# BATT_MONITOR.net
KiCad netlist of a schematic drawn in EAGLE
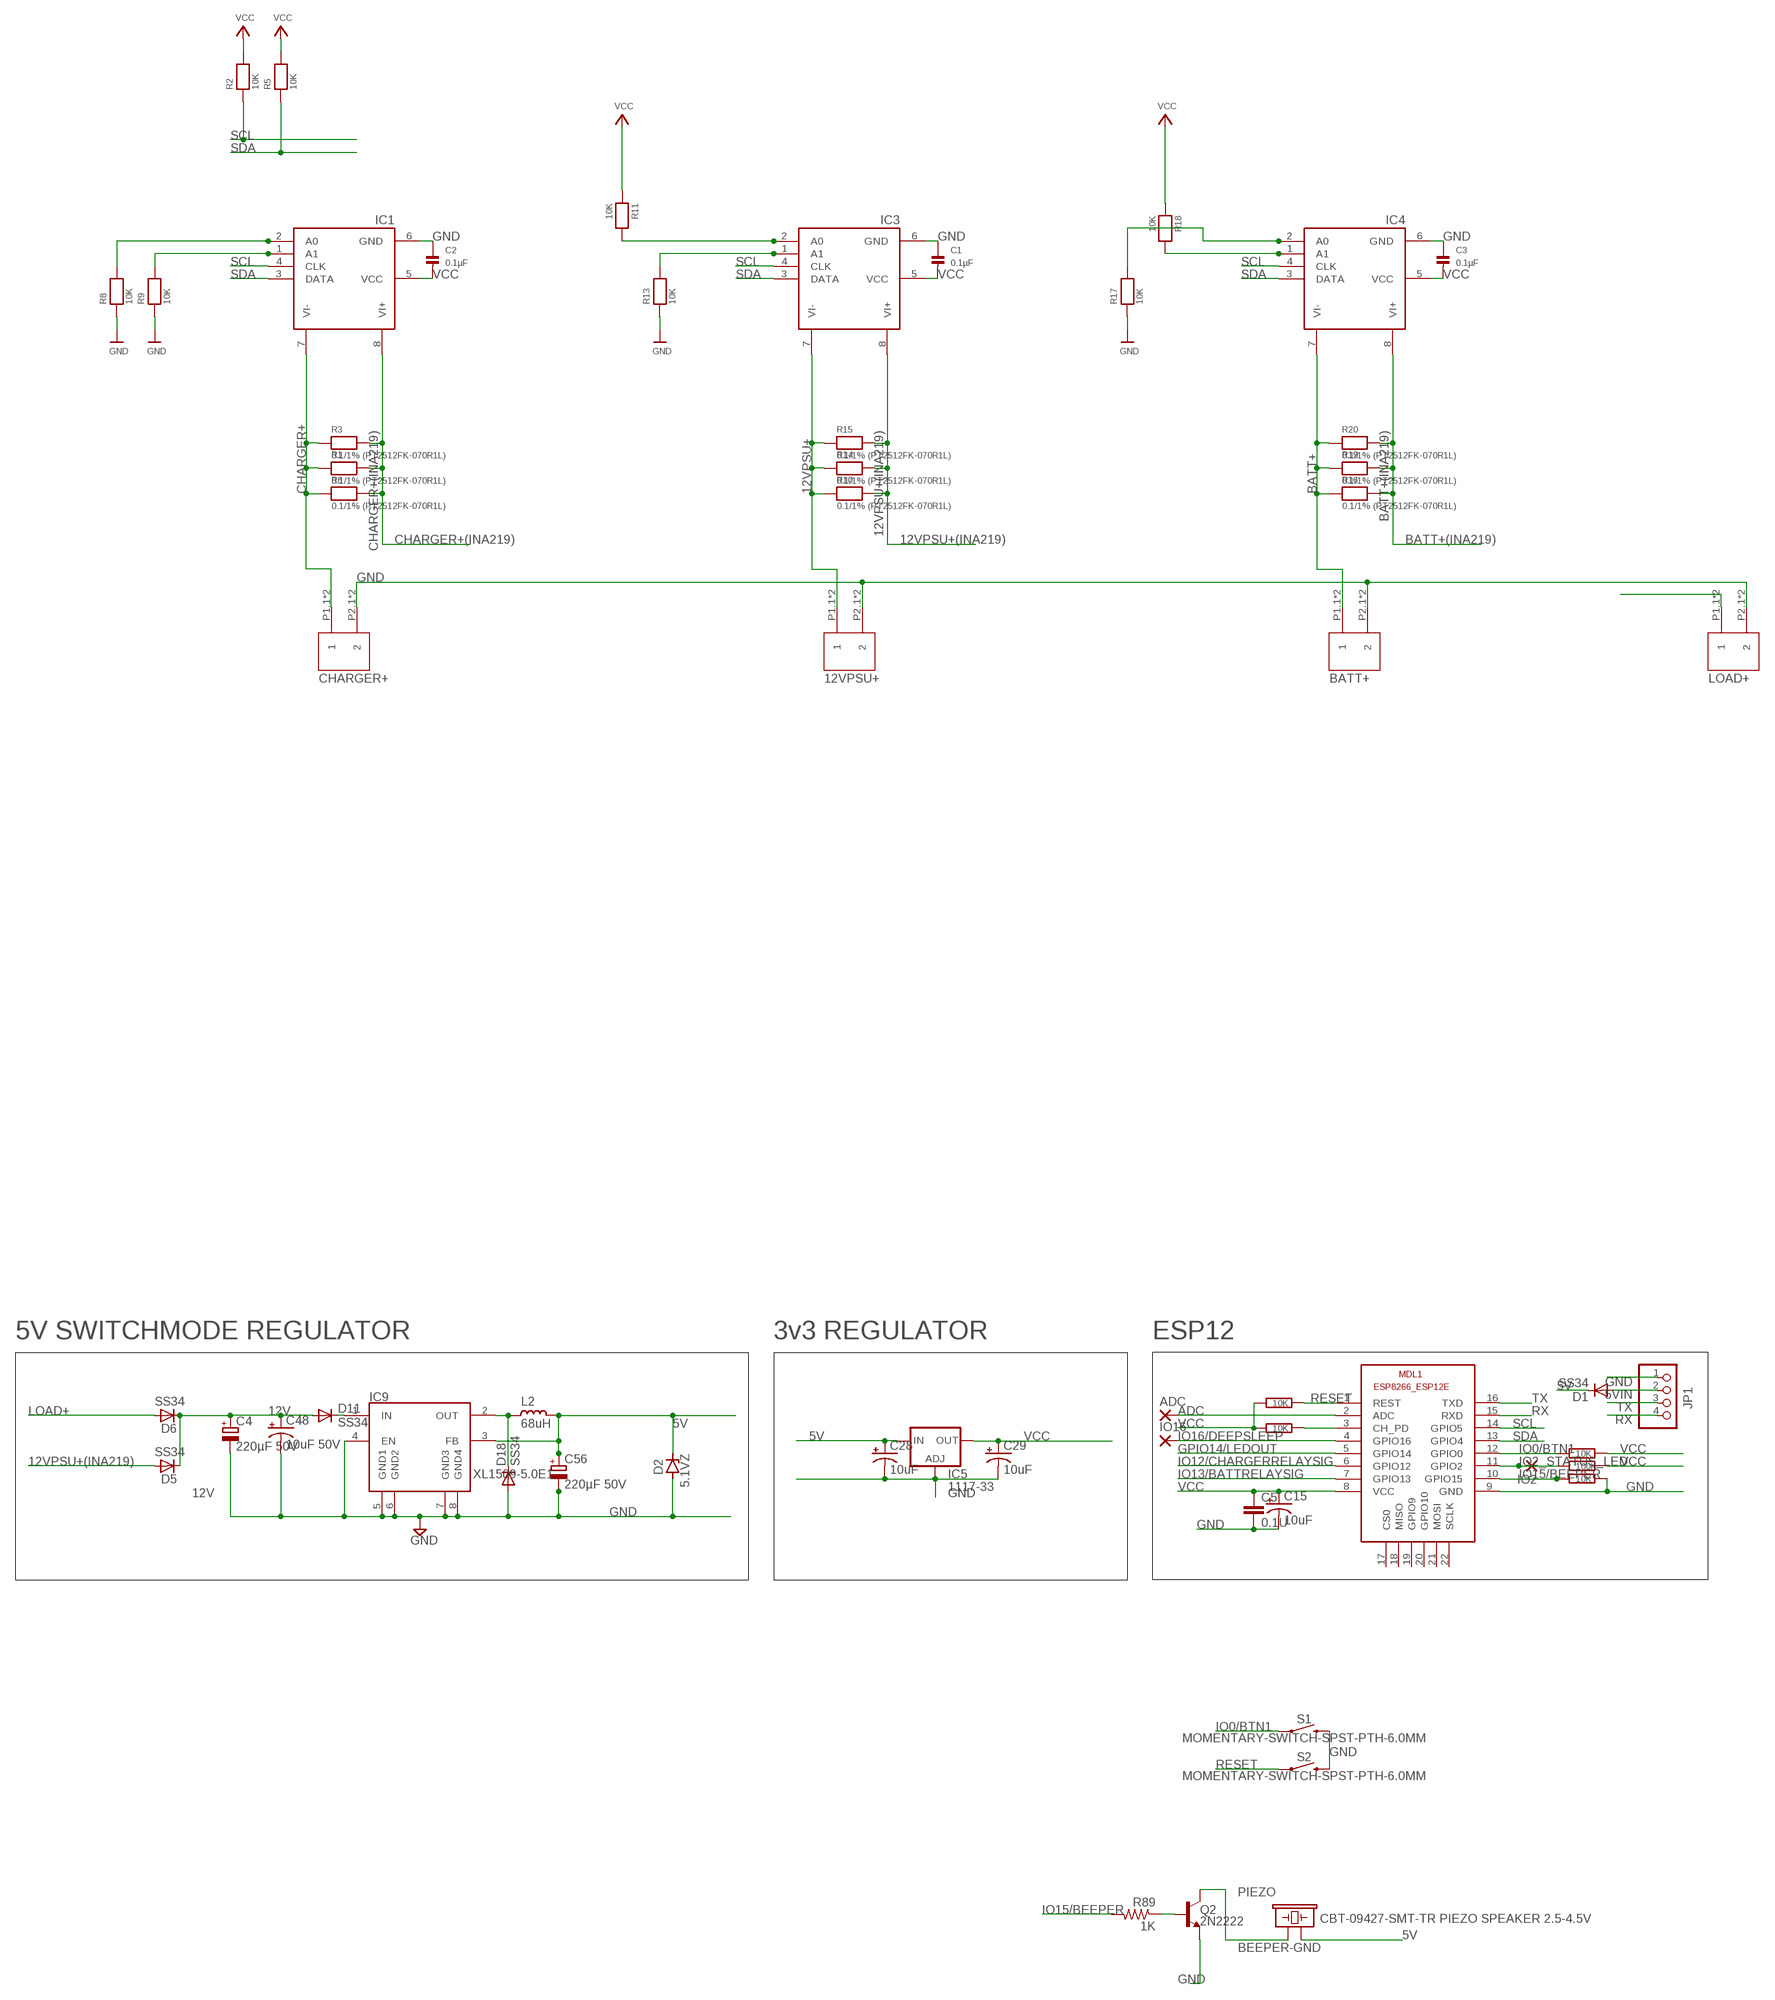
[diagram p0: schematic, sheet 2, part 1 of 2]
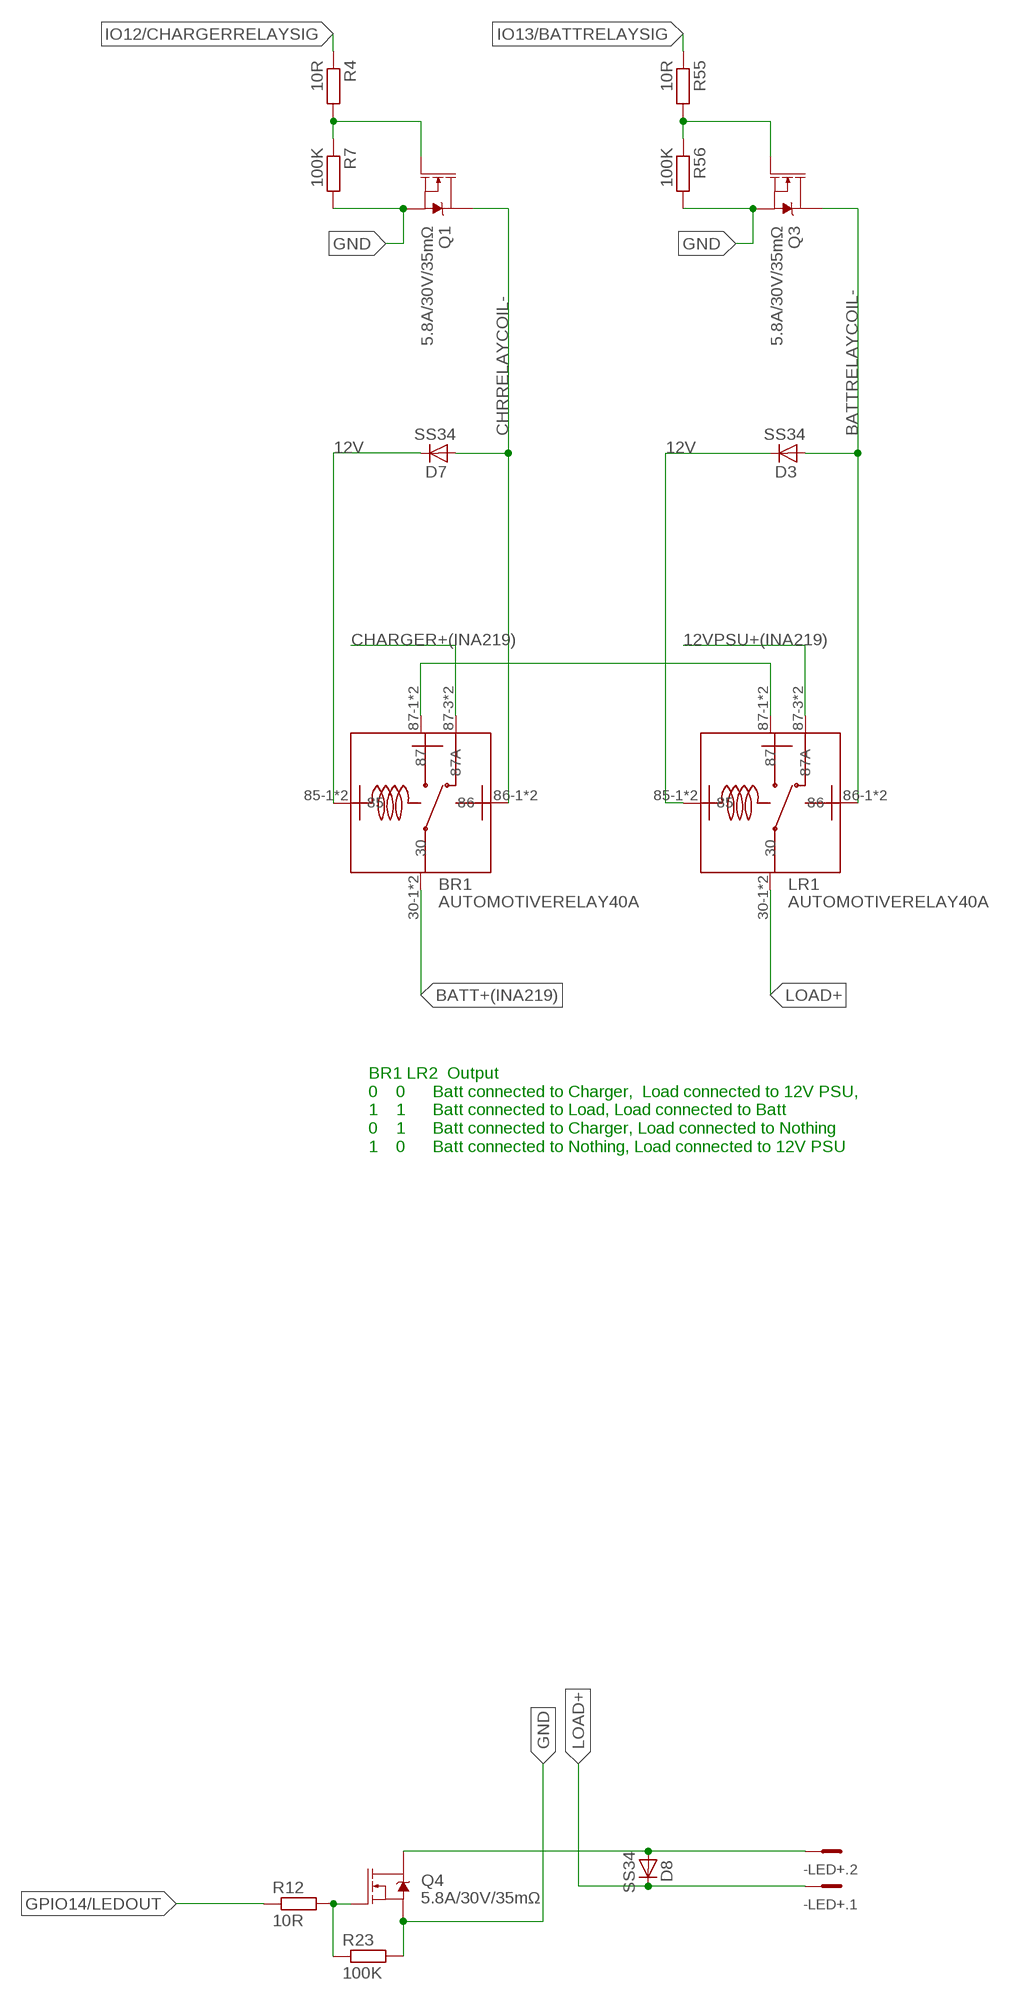
[diagram p1: schematic, sheet 2, part 2 of 2]

(export (version "E")
  (design (tool "Eeschema 10.0.6"))
  (components
    (comp (ref "-LED+")
      (value "MCV2")
      (footprint "eagle-import:MCV2")
      (libsource (lib "eagle-import") (part "MCV2"))
    )
    (comp (ref "ADC")
      (value "2,54/1,1")
      (footprint "eagle-import:2,54_1,1")
      (libsource (lib "eagle-import") (part "2,54/1,1"))
    )
    (comp (ref "BR1")
      (value "AUTOMOTIVERELAY40A")
      (footprint "eagle-import:AUTOMOTIVERELAY40A")
      (libsource (lib "eagle-import") (part "AUTOMOTIVERELAY40A"))
    )
    (comp (ref "C1")
      (value "0.1µF")
      (footprint "eagle-import:1206")
      (libsource (lib "eagle-import") (part "CAP_CERAMIC1206"))
    )
    (comp (ref "C2")
      (value "0.1µF")
      (footprint "eagle-import:1206")
      (libsource (lib "eagle-import") (part "CAP_CERAMIC1206"))
    )
    (comp (ref "C3")
      (value "0.1µF")
      (footprint "eagle-import:1206")
      (libsource (lib "eagle-import") (part "CAP_CERAMIC1206"))
    )
    (comp (ref "C4")
      (value "220µF 50V")
      (footprint "eagle-import:E3,5-10")
      (libsource (lib "eagle-import") (part "CPOL-EUE3.5-10"))
    )
    (comp (ref "C5")
      (value "0.1U")
      (footprint "eagle-import:C1206")
      (libsource (lib "eagle-import") (part "C-EUC1206"))
    )
    (comp (ref "C15")
      (value "10uF")
      (footprint "eagle-import:EIA3216")
      (libsource (lib "eagle-import") (part "CAP_POL1206"))
    )
    (comp (ref "C28")
      (value "10uF")
      (footprint "eagle-import:EIA3216")
      (libsource (lib "eagle-import") (part "CAP_POL1206"))
    )
    (comp (ref "C29")
      (value "10uF")
      (footprint "eagle-import:EIA3216")
      (libsource (lib "eagle-import") (part "CAP_POL1206"))
    )
    (comp (ref "C48")
      (value "10uF 50V")
      (footprint "eagle-import:EIA3216")
      (libsource (lib "eagle-import") (part "CAP_POL1206"))
    )
    (comp (ref "C56")
      (value "220µF 50V")
      (footprint "eagle-import:E3,5-10")
      (libsource (lib "eagle-import") (part "CPOL-EUE3.5-10"))
    )
    (comp (ref "CHARGER1")
      (value "BARRIERTERMINAL")
      (footprint "eagle-import:BARRIERTERMINAL")
      (libsource (lib "eagle-import") (part "BARRIERTERMINAL"))
    )
    (comp (ref "CHARGER2")
      (value "BARRIERTERMINAL")
      (footprint "eagle-import:BARRIERTERMINAL")
      (libsource (lib "eagle-import") (part "BARRIERTERMINAL"))
    )
    (comp (ref "CHARGER3")
      (value "BARRIERTERMINAL")
      (footprint "eagle-import:BARRIERTERMINAL")
      (libsource (lib "eagle-import") (part "BARRIERTERMINAL"))
    )
    (comp (ref "CHARGER4")
      (value "BARRIERTERMINAL")
      (footprint "eagle-import:BARRIERTERMINAL")
      (libsource (lib "eagle-import") (part "BARRIERTERMINAL"))
    )
    (comp (ref "D1")
      (value "SS34")
      (footprint "eagle-import:DO-214AC")
      (libsource (lib "eagle-import") (part "DIODE-DO-214AC"))
    )
    (comp (ref "D2")
      (value "5.1VZ")
      (footprint "eagle-import:SMB")
      (libsource (lib "eagle-import") (part "ZENER-DIODESMB"))
    )
    (comp (ref "D3")
      (value "SS34")
      (footprint "eagle-import:SOD87")
      (libsource (lib "eagle-import") (part "D-SOD-87"))
    )
    (comp (ref "D5")
      (value "SS34")
      (footprint "eagle-import:SOD87")
      (libsource (lib "eagle-import") (part "D-SOD-87"))
    )
    (comp (ref "D6")
      (value "SS34")
      (footprint "eagle-import:SOD87")
      (libsource (lib "eagle-import") (part "D-SOD-87"))
    )
    (comp (ref "D7")
      (value "SS34")
      (footprint "eagle-import:SOD87")
      (libsource (lib "eagle-import") (part "D-SOD-87"))
    )
    (comp (ref "D8")
      (value "SS34")
      (footprint "eagle-import:SOD87")
      (libsource (lib "eagle-import") (part "D-SOD-87"))
    )
    (comp (ref "D11")
      (value "SS34")
      (footprint "eagle-import:DO-214AC")
      (libsource (lib "eagle-import") (part "DIODE-DO-214AC"))
    )
    (comp (ref "D18")
      (value "SS34")
      (footprint "eagle-import:DO-214AC")
      (libsource (lib "eagle-import") (part "DIODE-DO-214AC"))
    )
    (comp (ref "IC1")
      (value "INA219D")
      (footprint "eagle-import:SO08")
      (libsource (lib "eagle-import") (part "INA219D"))
    )
    (comp (ref "IC3")
      (value "INA219D")
      (footprint "eagle-import:SO08")
      (libsource (lib "eagle-import") (part "INA219D"))
    )
    (comp (ref "IC4")
      (value "INA219D")
      (footprint "eagle-import:SO08")
      (libsource (lib "eagle-import") (part "INA219D"))
    )
    (comp (ref "IC5")
      (value "1117-33")
      (footprint "eagle-import:SOT223")
      (libsource (lib "eagle-import") (part "LD117A?S33TR"))
    )
    (comp (ref "IC9")
      (value "XL1509-5.0E1")
      (footprint "eagle-import:SO08")
      (libsource (lib "eagle-import") (part "XL1509"))
    )
    (comp (ref "IO2")
      (value "2,54/1,1")
      (footprint "eagle-import:2,54_1,1")
      (libsource (lib "eagle-import") (part "2,54/1,1"))
    )
    (comp (ref "IO16")
      (value "2,54/1,1")
      (footprint "eagle-import:2,54_1,1")
      (libsource (lib "eagle-import") (part "2,54/1,1"))
    )
    (comp (ref "JP1")
      (value "PINHD-1X4")
      (footprint "eagle-import:1X04")
      (libsource (lib "eagle-import") (part "PINHD-1X4"))
    )
    (comp (ref "L2")
      (value "68uH")
      (footprint "eagle-import:CD75")
      (libsource (lib "eagle-import") (part "L_CD75"))
    )
    (comp (ref "LR1")
      (value "AUTOMOTIVERELAY40A")
      (footprint "eagle-import:AUTOMOTIVERELAY40A")
      (libsource (lib "eagle-import") (part "AUTOMOTIVERELAY40A"))
    )
    (comp (ref "MDL1")
      (value "ESP8266-12EESP8266-ESP12E")
      (footprint "eagle-import:ESP8266-ESP12E")
      (libsource (lib "eagle-import") (part "ESP8266-12EESP8266-ESP12E"))
    )
    (comp (ref "PIEZO")
      (value "CBT-09427-SMT-TR PIEZO SPEAKER 2.5-4.5V")
      (footprint "eagle-import:BUZZER-12MM")
      (libsource (lib "eagle-import") (part "BUZZER-PTH"))
    )
    (comp (ref "Q1")
      (value "5.8A/30V/35mΩ")
      (footprint "eagle-import:SOT23-3")
      (libsource (lib "eagle-import") (part "MOSFET-NCH-AO3404A"))
    )
    (comp (ref "Q2")
      (value "2N2222")
      (footprint "eagle-import:SOT23-3")
      (libsource (lib "eagle-import") (part "TRANS_NPN-MMBT2222AL"))
    )
    (comp (ref "Q3")
      (value "5.8A/30V/35mΩ")
      (footprint "eagle-import:SOT23-3")
      (libsource (lib "eagle-import") (part "MOSFET-NCH-AO3404A"))
    )
    (comp (ref "Q4")
      (value "5.8A/30V/35mΩ")
      (footprint "eagle-import:SOT23-3")
      (libsource (lib "eagle-import") (part "MOSFET-NCH-AO3404A"))
    )
    (comp (ref "R1")
      (value "0.1/1% (PT2512FK-070R1L)")
      (footprint "eagle-import:2512")
      (libsource (lib "eagle-import") (part "RESISTOR2512"))
    )
    (comp (ref "R2")
      (value "10K")
      (footprint "eagle-import:1206")
      (libsource (lib "eagle-import") (part "RESISTOR1206"))
    )
    (comp (ref "R3")
      (value "0.1/1% (PT2512FK-070R1L)")
      (footprint "eagle-import:2512")
      (libsource (lib "eagle-import") (part "RESISTOR2512"))
    )
    (comp (ref "R4")
      (value "10R")
      (footprint "eagle-import:R1206")
      (libsource (lib "eagle-import") (part "rcl_334_R-EU_R1206"))
    )
    (comp (ref "R5")
      (value "10K")
      (footprint "eagle-import:1206")
      (libsource (lib "eagle-import") (part "RESISTOR1206"))
    )
    (comp (ref "R6")
      (value "0.1/1% (PT2512FK-070R1L)")
      (footprint "eagle-import:2512")
      (libsource (lib "eagle-import") (part "RESISTOR2512"))
    )
    (comp (ref "R7")
      (value "100K")
      (footprint "eagle-import:R1206")
      (libsource (lib "eagle-import") (part "rcl_334_R-EU_R1206"))
    )
    (comp (ref "R8")
      (value "10K")
      (footprint "eagle-import:1206")
      (libsource (lib "eagle-import") (part "RESISTOR1206"))
    )
    (comp (ref "R9")
      (value "10K")
      (footprint "eagle-import:1206")
      (libsource (lib "eagle-import") (part "RESISTOR1206"))
    )
    (comp (ref "R10")
      (value "0.1/1% (PT2512FK-070R1L)")
      (footprint "eagle-import:2512")
      (libsource (lib "eagle-import") (part "RESISTOR2512"))
    )
    (comp (ref "R11")
      (value "10K")
      (footprint "eagle-import:1206")
      (libsource (lib "eagle-import") (part "RESISTOR1206"))
    )
    (comp (ref "R12")
      (value "10R")
      (footprint "eagle-import:M1206")
      (libsource (lib "eagle-import") (part "rcl_334_R-EU_M1206"))
    )
    (comp (ref "R13")
      (value "10K")
      (footprint "eagle-import:1206")
      (libsource (lib "eagle-import") (part "RESISTOR1206"))
    )
    (comp (ref "R14")
      (value "0.1/1% (PT2512FK-070R1L)")
      (footprint "eagle-import:2512")
      (libsource (lib "eagle-import") (part "RESISTOR2512"))
    )
    (comp (ref "R15")
      (value "0.1/1% (PT2512FK-070R1L)")
      (footprint "eagle-import:2512")
      (libsource (lib "eagle-import") (part "RESISTOR2512"))
    )
    (comp (ref "R16")
      (value "0.1/1% (PT2512FK-070R1L)")
      (footprint "eagle-import:2512")
      (libsource (lib "eagle-import") (part "RESISTOR2512"))
    )
    (comp (ref "R17")
      (value "10K")
      (footprint "eagle-import:1206")
      (libsource (lib "eagle-import") (part "RESISTOR1206"))
    )
    (comp (ref "R18")
      (value "10K")
      (footprint "eagle-import:1206")
      (libsource (lib "eagle-import") (part "RESISTOR1206"))
    )
    (comp (ref "R19")
      (value "0.1/1% (PT2512FK-070R1L)")
      (footprint "eagle-import:2512")
      (libsource (lib "eagle-import") (part "RESISTOR2512"))
    )
    (comp (ref "R20")
      (value "0.1/1% (PT2512FK-070R1L)")
      (footprint "eagle-import:2512")
      (libsource (lib "eagle-import") (part "RESISTOR2512"))
    )
    (comp (ref "R21")
      (value "100K")
      (footprint "eagle-import:R1206")
      (libsource (lib "eagle-import") (part "R-EU_R1206"))
    )
    (comp (ref "R22")
      (value "10K")
      (footprint "eagle-import:R1206")
      (libsource (lib "eagle-import") (part "R-EU_R1206"))
    )
    (comp (ref "R23")
      (value "100K")
      (footprint "eagle-import:M1206")
      (libsource (lib "eagle-import") (part "rcl_334_R-EU_M1206"))
    )
    (comp (ref "R28")
      (value "10K")
      (footprint "eagle-import:R1206")
      (libsource (lib "eagle-import") (part "R-EU_R1206"))
    )
    (comp (ref "R29")
      (value "10K")
      (footprint "eagle-import:R1206")
      (libsource (lib "eagle-import") (part "R-EU_R1206"))
    )
    (comp (ref "R31")
      (value "10K")
      (footprint "eagle-import:R1206")
      (libsource (lib "eagle-import") (part "R-EU_R1206"))
    )
    (comp (ref "R55")
      (value "10R")
      (footprint "eagle-import:R1206")
      (libsource (lib "eagle-import") (part "rcl_334_R-EU_R1206"))
    )
    (comp (ref "R56")
      (value "100K")
      (footprint "eagle-import:R1206")
      (libsource (lib "eagle-import") (part "rcl_334_R-EU_R1206"))
    )
    (comp (ref "R89")
      (value "1K")
      (footprint "eagle-import:R1206")
      (libsource (lib "eagle-import") (part "R-US_R1206"))
    )
    (comp (ref "S1")
      (value "MOMENTARY-SWITCH-SPST-PTH-6.0MM")
      (footprint "eagle-import:TACTILE_SWITCH_PTH_6.0MM")
      (libsource (lib "eagle-import") (part "MOMENTARY-SWITCH-SPST-PTH-6.0MM"))
    )
    (comp (ref "S2")
      (value "MOMENTARY-SWITCH-SPST-PTH-6.0MM")
      (footprint "eagle-import:TACTILE_SWITCH_PTH_6.0MM")
      (libsource (lib "eagle-import") (part "MOMENTARY-SWITCH-SPST-PTH-6.0MM"))
    )
  )
  (nets
    (net (code "1") (name "5V") (class "Default")
      (node (ref "C28") (pin "A") (pinfunction "+_A") (pintype "passive"))
      (node (ref "C56") (pin "+") (pinfunction "+_+") (pintype "passive"))
      (node (ref "D1") (pin "1") (pinfunction "C_1") (pintype "passive"))
      (node (ref "D2") (pin "C") (pinfunction "C_C") (pintype "passive"))
      (node (ref "IC5") (pin "3") (pinfunction "IN_3") (pintype "input"))
      (node (ref "IC9") (pin "3") (pinfunction "FB_3") (pintype "bidirectional"))
      (node (ref "L2") (pin "1") (pinfunction "1_1") (pintype "passive"))
      (node (ref "PIEZO") (pin "+") (pinfunction "1_+") (pintype "passive"))
    )
    (net (code "2") (name "5VIN") (class "Default")
      (node (ref "D1") (pin "2") (pinfunction "A_2") (pintype "passive"))
      (node (ref "JP1") (pin "2") (pinfunction "2_2") (pintype "passive"))
    )
    (net (code "3") (name "12V") (class "Default")
      (node (ref "BR1") (pin "85-1") (pinfunction "85_85-1") (pintype "bidirectional"))
      (node (ref "BR1") (pin "85-2") (pinfunction "85_85-2") (pintype "bidirectional"))
      (node (ref "C4") (pin "+") (pinfunction "+_+") (pintype "passive"))
      (node (ref "C48") (pin "A") (pinfunction "+_A") (pintype "passive"))
      (node (ref "D11") (pin "2") (pinfunction "A_2") (pintype "passive"))
      (node (ref "D3") (pin "1") (pinfunction "C_1") (pintype "passive"))
      (node (ref "D5") (pin "1") (pinfunction "C_1") (pintype "passive"))
      (node (ref "D6") (pin "1") (pinfunction "C_1") (pintype "passive"))
      (node (ref "D7") (pin "1") (pinfunction "C_1") (pintype "passive"))
      (node (ref "LR1") (pin "85-1") (pinfunction "85_85-1") (pintype "bidirectional"))
      (node (ref "LR1") (pin "85-2") (pinfunction "85_85-2") (pintype "bidirectional"))
    )
    (net (code "4") (name "12VPSU+") (class "Default")
      (node (ref "CHARGER4") (pin "P1.1") (pinfunction "1_P1.1") (pintype "bidirectional"))
      (node (ref "CHARGER4") (pin "P1.2") (pinfunction "1_P1.2") (pintype "bidirectional"))
      (node (ref "IC3") (pin "7") (pinfunction "VI-_7") (pintype "input"))
      (node (ref "R10") (pin "1") (pinfunction "1_1") (pintype "passive"))
      (node (ref "R14") (pin "1") (pinfunction "1_1") (pintype "passive"))
      (node (ref "R15") (pin "1") (pinfunction "1_1") (pintype "passive"))
    )
    (net (code "5") (name "12VPSU+(INA219)") (class "Default")
      (node (ref "D5") (pin "2") (pinfunction "A_2") (pintype "passive"))
      (node (ref "IC3") (pin "8") (pinfunction "VI+_8") (pintype "input"))
      (node (ref "LR1") (pin "87-3") (pinfunction "87A_87-3") (pintype "bidirectional"))
      (node (ref "LR1") (pin "87-4") (pinfunction "87A_87-4") (pintype "bidirectional"))
      (node (ref "R10") (pin "2") (pinfunction "2_2") (pintype "passive"))
      (node (ref "R14") (pin "2") (pinfunction "2_2") (pintype "passive"))
      (node (ref "R15") (pin "2") (pinfunction "2_2") (pintype "passive"))
    )
    (net (code "6") (name "ADC") (class "Default")
      (node (ref "ADC") (pin "1") (pinfunction "P_1") (pintype "passive"))
      (node (ref "MDL1") (pin "2") (pinfunction "ADC_2") (pintype "bidirectional"))
    )
    (net (code "7") (name "BATT+") (class "Default")
      (node (ref "CHARGER1") (pin "P1.1") (pinfunction "1_P1.1") (pintype "bidirectional"))
      (node (ref "CHARGER1") (pin "P1.2") (pinfunction "1_P1.2") (pintype "bidirectional"))
      (node (ref "IC4") (pin "7") (pinfunction "VI-_7") (pintype "input"))
      (node (ref "R16") (pin "1") (pinfunction "1_1") (pintype "passive"))
      (node (ref "R19") (pin "1") (pinfunction "1_1") (pintype "passive"))
      (node (ref "R20") (pin "1") (pinfunction "1_1") (pintype "passive"))
    )
    (net (code "8") (name "BATT+(INA219)") (class "Default")
      (node (ref "BR1") (pin "30-1") (pinfunction "30_30-1") (pintype "bidirectional"))
      (node (ref "BR1") (pin "30-2") (pinfunction "30_30-2") (pintype "bidirectional"))
      (node (ref "IC4") (pin "8") (pinfunction "VI+_8") (pintype "input"))
      (node (ref "R16") (pin "2") (pinfunction "2_2") (pintype "passive"))
      (node (ref "R19") (pin "2") (pinfunction "2_2") (pintype "passive"))
      (node (ref "R20") (pin "2") (pinfunction "2_2") (pintype "passive"))
    )
    (net (code "9") (name "BATTRELAYCOIL-") (class "Default")
      (node (ref "D3") (pin "2") (pinfunction "A_2") (pintype "passive"))
      (node (ref "LR1") (pin "86-1") (pinfunction "86_86-1") (pintype "bidirectional"))
      (node (ref "LR1") (pin "86-2") (pinfunction "86_86-2") (pintype "bidirectional"))
      (node (ref "Q3") (pin "3") (pinfunction "D_3") (pintype "bidirectional"))
    )
    (net (code "10") (name "BEEPER-GND") (class "Default")
      (node (ref "PIEZO") (pin "-") (pinfunction "2_-") (pintype "passive"))
      (node (ref "Q2") (pin "3") (pinfunction "C_3") (pintype "passive"))
    )
    (net (code "11") (name "CHARGER+") (class "Default")
      (node (ref "CHARGER3") (pin "P1.1") (pinfunction "1_P1.1") (pintype "bidirectional"))
      (node (ref "CHARGER3") (pin "P1.2") (pinfunction "1_P1.2") (pintype "bidirectional"))
      (node (ref "IC1") (pin "7") (pinfunction "VI-_7") (pintype "input"))
      (node (ref "R1") (pin "1") (pinfunction "1_1") (pintype "passive"))
      (node (ref "R3") (pin "1") (pinfunction "1_1") (pintype "passive"))
      (node (ref "R6") (pin "1") (pinfunction "1_1") (pintype "passive"))
    )
    (net (code "12") (name "CHARGER+(INA219)") (class "Default")
      (node (ref "BR1") (pin "87-3") (pinfunction "87A_87-3") (pintype "bidirectional"))
      (node (ref "BR1") (pin "87-4") (pinfunction "87A_87-4") (pintype "bidirectional"))
      (node (ref "IC1") (pin "8") (pinfunction "VI+_8") (pintype "input"))
      (node (ref "R1") (pin "2") (pinfunction "2_2") (pintype "passive"))
      (node (ref "R3") (pin "2") (pinfunction "2_2") (pintype "passive"))
      (node (ref "R6") (pin "2") (pinfunction "2_2") (pintype "passive"))
    )
    (net (code "13") (name "CHRRELAYCOIL-") (class "Default")
      (node (ref "BR1") (pin "86-1") (pinfunction "86_86-1") (pintype "bidirectional"))
      (node (ref "BR1") (pin "86-2") (pinfunction "86_86-2") (pintype "bidirectional"))
      (node (ref "D7") (pin "2") (pinfunction "A_2") (pintype "passive"))
      (node (ref "Q1") (pin "3") (pinfunction "D_3") (pintype "bidirectional"))
    )
    (net (code "14") (name "GND") (class "Default")
      (node (ref "C1") (pin "1") (pinfunction "P$1_1") (pintype "passive"))
      (node (ref "C15") (pin "C") (pinfunction "-_C") (pintype "passive"))
      (node (ref "C2") (pin "1") (pinfunction "P$1_1") (pintype "passive"))
      (node (ref "C28") (pin "C") (pinfunction "-_C") (pintype "passive"))
      (node (ref "C29") (pin "C") (pinfunction "-_C") (pintype "passive"))
      (node (ref "C3") (pin "1") (pinfunction "P$1_1") (pintype "passive"))
      (node (ref "C4") (pin "-") (pinfunction "-_-") (pintype "passive"))
      (node (ref "C48") (pin "C") (pinfunction "-_C") (pintype "passive"))
      (node (ref "C5") (pin "2") (pinfunction "2_2") (pintype "passive"))
      (node (ref "C56") (pin "-") (pinfunction "-_-") (pintype "passive"))
      (node (ref "CHARGER1") (pin "P2.1") (pinfunction "2_P2.1") (pintype "bidirectional"))
      (node (ref "CHARGER1") (pin "P2.2") (pinfunction "2_P2.2") (pintype "bidirectional"))
      (node (ref "CHARGER2") (pin "P2.1") (pinfunction "2_P2.1") (pintype "bidirectional"))
      (node (ref "CHARGER2") (pin "P2.2") (pinfunction "2_P2.2") (pintype "bidirectional"))
      (node (ref "CHARGER3") (pin "P2.1") (pinfunction "2_P2.1") (pintype "bidirectional"))
      (node (ref "CHARGER3") (pin "P2.2") (pinfunction "2_P2.2") (pintype "bidirectional"))
      (node (ref "CHARGER4") (pin "P2.1") (pinfunction "2_P2.1") (pintype "bidirectional"))
      (node (ref "CHARGER4") (pin "P2.2") (pinfunction "2_P2.2") (pintype "bidirectional"))
      (node (ref "D18") (pin "2") (pinfunction "A_2") (pintype "passive"))
      (node (ref "D2") (pin "A") (pinfunction "A_A") (pintype "passive"))
      (node (ref "IC1") (pin "6") (pinfunction "GND_6") (pintype "power_in"))
      (node (ref "IC3") (pin "6") (pinfunction "GND_6") (pintype "power_in"))
      (node (ref "IC4") (pin "6") (pinfunction "GND_6") (pintype "power_in"))
      (node (ref "IC5") (pin "1") (pinfunction "ADJ_1") (pintype "input"))
      (node (ref "IC9") (pin "4") (pinfunction "EN_4") (pintype "bidirectional"))
      (node (ref "IC9") (pin "5") (pinfunction "GND1_5") (pintype "bidirectional"))
      (node (ref "IC9") (pin "6") (pinfunction "GND2_6") (pintype "bidirectional"))
      (node (ref "IC9") (pin "7") (pinfunction "GND3_7") (pintype "bidirectional"))
      (node (ref "IC9") (pin "8") (pinfunction "GND4_8") (pintype "bidirectional"))
      (node (ref "JP1") (pin "1") (pinfunction "1_1") (pintype "passive"))
      (node (ref "MDL1") (pin "9") (pinfunction "GND_9") (pintype "bidirectional"))
      (node (ref "Q1") (pin "2") (pinfunction "S_2") (pintype "bidirectional"))
      (node (ref "Q2") (pin "2") (pinfunction "E_2") (pintype "passive"))
      (node (ref "Q3") (pin "2") (pinfunction "S_2") (pintype "bidirectional"))
      (node (ref "Q4") (pin "2") (pinfunction "S_2") (pintype "bidirectional"))
      (node (ref "R13") (pin "1") (pinfunction "1_1") (pintype "passive"))
      (node (ref "R17") (pin "1") (pinfunction "1_1") (pintype "passive"))
      (node (ref "R23") (pin "2") (pinfunction "2_2") (pintype "passive"))
      (node (ref "R31") (pin "2") (pinfunction "2_2") (pintype "passive"))
      (node (ref "R56") (pin "2") (pinfunction "2_2") (pintype "passive"))
      (node (ref "R7") (pin "2") (pinfunction "2_2") (pintype "passive"))
      (node (ref "R8") (pin "1") (pinfunction "1_1") (pintype "passive"))
      (node (ref "R9") (pin "1") (pinfunction "1_1") (pintype "passive"))
      (node (ref "S1") (pin "3") (pinfunction "2_3") (pintype "passive"))
      (node (ref "S2") (pin "3") (pinfunction "2_3") (pintype "passive"))
    )
    (net (code "15") (name "GPIO14{slash}LEDOUT") (class "Default")
      (node (ref "MDL1") (pin "5") (pinfunction "GPIO14_5") (pintype "bidirectional"))
      (node (ref "R12") (pin "1") (pinfunction "1_1") (pintype "passive"))
    )
    (net (code "16") (name "IO0{slash}BTN1") (class "Default")
      (node (ref "MDL1") (pin "12") (pinfunction "GPIO0_12") (pintype "bidirectional"))
      (node (ref "R22") (pin "1") (pinfunction "1_1") (pintype "passive"))
      (node (ref "S1") (pin "1") (pinfunction "1_1") (pintype "passive"))
    )
    (net (code "17") (name "IO2_STATUS_LED") (class "Default")
      (node (ref "IO2") (pin "1") (pinfunction "P_1") (pintype "passive"))
      (node (ref "MDL1") (pin "11") (pinfunction "GPIO2_11") (pintype "bidirectional"))
      (node (ref "R21") (pin "1") (pinfunction "1_1") (pintype "passive"))
    )
    (net (code "18") (name "IO12{slash}CHARGERRELAYSIG") (class "Default")
      (node (ref "MDL1") (pin "6") (pinfunction "GPIO12_6") (pintype "bidirectional"))
      (node (ref "R4") (pin "1") (pinfunction "1_1") (pintype "passive"))
    )
    (net (code "19") (name "IO13{slash}BATTRELAYSIG") (class "Default")
      (node (ref "MDL1") (pin "7") (pinfunction "GPIO13_7") (pintype "bidirectional"))
      (node (ref "R55") (pin "1") (pinfunction "1_1") (pintype "passive"))
    )
    (net (code "20") (name "IO15{slash}BEEPER") (class "Default")
      (node (ref "MDL1") (pin "10") (pinfunction "GPIO15_10") (pintype "bidirectional"))
      (node (ref "R31") (pin "1") (pinfunction "1_1") (pintype "passive"))
      (node (ref "R89") (pin "2") (pinfunction "2_2") (pintype "passive"))
    )
    (net (code "21") (name "IO16{slash}DEEPSLEEP") (class "Default")
      (node (ref "IO16") (pin "1") (pinfunction "P_1") (pintype "passive"))
      (node (ref "MDL1") (pin "4") (pinfunction "GPIO16_4") (pintype "bidirectional"))
    )
    (net (code "22") (name "LOAD+") (class "Default")
      (node (ref "-LED+") (pin "1") (pinfunction "SK_1") (pintype "passive"))
      (node (ref "CHARGER2") (pin "P1.1") (pinfunction "1_P1.1") (pintype "bidirectional"))
      (node (ref "CHARGER2") (pin "P1.2") (pinfunction "1_P1.2") (pintype "bidirectional"))
      (node (ref "D6") (pin "2") (pinfunction "A_2") (pintype "passive"))
      (node (ref "D8") (pin "1") (pinfunction "C_1") (pintype "passive"))
      (node (ref "LR1") (pin "30-1") (pinfunction "30_30-1") (pintype "bidirectional"))
      (node (ref "LR1") (pin "30-2") (pinfunction "30_30-2") (pintype "bidirectional"))
    )
    (net (code "23") (name "Net-(-LED+B-SK)") (class "Default")
      (node (ref "-LED+") (pin "2") (pinfunction "SK_2") (pintype "passive"))
      (node (ref "D8") (pin "2") (pinfunction "A_2") (pintype "passive"))
      (node (ref "Q4") (pin "3") (pinfunction "D_3") (pintype "bidirectional"))
    )
    (net (code "24") (name "Net-(BR1-87-Pad87-1)") (class "Default")
      (node (ref "BR1") (pin "87-1") (pinfunction "87_87-1") (pintype "bidirectional"))
      (node (ref "BR1") (pin "87-2") (pinfunction "87_87-2") (pintype "bidirectional"))
      (node (ref "LR1") (pin "87-1") (pinfunction "87_87-1") (pintype "bidirectional"))
      (node (ref "LR1") (pin "87-2") (pinfunction "87_87-2") (pintype "bidirectional"))
    )
    (net (code "25") (name "Net-(D11-C)") (class "Default")
      (node (ref "D11") (pin "1") (pinfunction "C_1") (pintype "passive"))
      (node (ref "IC9") (pin "1") (pinfunction "IN_1") (pintype "bidirectional"))
    )
    (net (code "26") (name "Net-(D18-C)") (class "Default")
      (node (ref "D18") (pin "1") (pinfunction "C_1") (pintype "passive"))
      (node (ref "IC9") (pin "2") (pinfunction "OUT_2") (pintype "bidirectional"))
      (node (ref "L2") (pin "2") (pinfunction "2_2") (pintype "passive"))
    )
    (net (code "27") (name "Net-(IC1-A0)") (class "Default")
      (node (ref "IC1") (pin "2") (pinfunction "A0_2") (pintype "input"))
      (node (ref "R8") (pin "2") (pinfunction "2_2") (pintype "passive"))
    )
    (net (code "28") (name "Net-(IC1-A1)") (class "Default")
      (node (ref "IC1") (pin "1") (pinfunction "A1_1") (pintype "input"))
      (node (ref "R9") (pin "2") (pinfunction "2_2") (pintype "passive"))
    )
    (net (code "29") (name "Net-(IC3-A0)") (class "Default")
      (node (ref "IC3") (pin "2") (pinfunction "A0_2") (pintype "input"))
      (node (ref "R11") (pin "2") (pinfunction "2_2") (pintype "passive"))
    )
    (net (code "30") (name "Net-(IC3-A1)") (class "Default")
      (node (ref "IC3") (pin "1") (pinfunction "A1_1") (pintype "input"))
      (node (ref "R13") (pin "2") (pinfunction "2_2") (pintype "passive"))
    )
    (net (code "31") (name "Net-(IC4-A0)") (class "Default")
      (node (ref "IC4") (pin "2") (pinfunction "A0_2") (pintype "input"))
      (node (ref "R17") (pin "2") (pinfunction "2_2") (pintype "passive"))
    )
    (net (code "32") (name "Net-(IC4-A1)") (class "Default")
      (node (ref "IC4") (pin "1") (pinfunction "A1_1") (pintype "input"))
      (node (ref "R18") (pin "2") (pinfunction "2_2") (pintype "passive"))
    )
    (net (code "33") (name "Net-(MDL1-CH_PD)") (class "Default")
      (node (ref "MDL1") (pin "3") (pinfunction "CH_PD_3") (pintype "bidirectional"))
      (node (ref "R28") (pin "2") (pinfunction "2_2") (pintype "passive"))
    )
    (net (code "34") (name "Net-(Q1-G)") (class "Default")
      (node (ref "Q1") (pin "1") (pinfunction "G_1") (pintype "bidirectional"))
      (node (ref "R4") (pin "2") (pinfunction "2_2") (pintype "passive"))
      (node (ref "R7") (pin "1") (pinfunction "1_1") (pintype "passive"))
    )
    (net (code "35") (name "Net-(Q2-B)") (class "Default")
      (node (ref "Q2") (pin "1") (pinfunction "B_1") (pintype "passive"))
      (node (ref "R89") (pin "1") (pinfunction "1_1") (pintype "passive"))
    )
    (net (code "36") (name "Net-(Q3-G)") (class "Default")
      (node (ref "Q3") (pin "1") (pinfunction "G_1") (pintype "bidirectional"))
      (node (ref "R55") (pin "2") (pinfunction "2_2") (pintype "passive"))
      (node (ref "R56") (pin "1") (pinfunction "1_1") (pintype "passive"))
    )
    (net (code "37") (name "Net-(Q4-G)") (class "Default")
      (node (ref "Q4") (pin "1") (pinfunction "G_1") (pintype "bidirectional"))
      (node (ref "R12") (pin "2") (pinfunction "2_2") (pintype "passive"))
      (node (ref "R23") (pin "1") (pinfunction "1_1") (pintype "passive"))
    )
    (net (code "38") (name "RESET") (class "Default")
      (node (ref "MDL1") (pin "1") (pinfunction "REST_1") (pintype "bidirectional"))
      (node (ref "R29") (pin "2") (pinfunction "2_2") (pintype "passive"))
      (node (ref "S2") (pin "1") (pinfunction "1_1") (pintype "passive"))
    )
    (net (code "39") (name "RX") (class "Default")
      (node (ref "JP1") (pin "4") (pinfunction "4_4") (pintype "passive"))
      (node (ref "MDL1") (pin "15") (pinfunction "RXD_15") (pintype "bidirectional"))
    )
    (net (code "40") (name "SCL") (class "Default")
      (node (ref "IC1") (pin "4") (pinfunction "CLK_4") (pintype "input"))
      (node (ref "IC3") (pin "4") (pinfunction "CLK_4") (pintype "input"))
      (node (ref "IC4") (pin "4") (pinfunction "CLK_4") (pintype "input"))
      (node (ref "MDL1") (pin "14") (pinfunction "GPIO5_14") (pintype "bidirectional"))
      (node (ref "R2") (pin "1") (pinfunction "1_1") (pintype "passive"))
    )
    (net (code "41") (name "SDA") (class "Default")
      (node (ref "IC1") (pin "3") (pinfunction "DATA_3") (pintype "input"))
      (node (ref "IC3") (pin "3") (pinfunction "DATA_3") (pintype "input"))
      (node (ref "IC4") (pin "3") (pinfunction "DATA_3") (pintype "input"))
      (node (ref "MDL1") (pin "13") (pinfunction "GPIO4_13") (pintype "bidirectional"))
      (node (ref "R5") (pin "1") (pinfunction "1_1") (pintype "passive"))
    )
    (net (code "42") (name "TX") (class "Default")
      (node (ref "JP1") (pin "3") (pinfunction "3_3") (pintype "passive"))
      (node (ref "MDL1") (pin "16") (pinfunction "TXD_16") (pintype "bidirectional"))
    )
    (net (code "43") (name "VCC") (class "Default")
      (node (ref "C1") (pin "2") (pinfunction "P$2_2") (pintype "passive"))
      (node (ref "C15") (pin "A") (pinfunction "+_A") (pintype "passive"))
      (node (ref "C2") (pin "2") (pinfunction "P$2_2") (pintype "passive"))
      (node (ref "C29") (pin "A") (pinfunction "+_A") (pintype "passive"))
      (node (ref "C3") (pin "2") (pinfunction "P$2_2") (pintype "passive"))
      (node (ref "C5") (pin "1") (pinfunction "1_1") (pintype "passive"))
      (node (ref "IC1") (pin "5") (pinfunction "VCC_5") (pintype "power_in"))
      (node (ref "IC3") (pin "5") (pinfunction "VCC_5") (pintype "power_in"))
      (node (ref "IC4") (pin "5") (pinfunction "VCC_5") (pintype "power_in"))
      (node (ref "IC5") (pin "4") (pinfunction "OUT_4") (pintype "passive"))
      (node (ref "MDL1") (pin "8") (pinfunction "VCC_8") (pintype "bidirectional"))
      (node (ref "R11") (pin "1") (pinfunction "1_1") (pintype "passive"))
      (node (ref "R18") (pin "1") (pinfunction "1_1") (pintype "passive"))
      (node (ref "R2") (pin "2") (pinfunction "2_2") (pintype "passive"))
      (node (ref "R21") (pin "2") (pinfunction "2_2") (pintype "passive"))
      (node (ref "R22") (pin "2") (pinfunction "2_2") (pintype "passive"))
      (node (ref "R28") (pin "1") (pinfunction "1_1") (pintype "passive"))
      (node (ref "R29") (pin "1") (pinfunction "1_1") (pintype "passive"))
      (node (ref "R5") (pin "2") (pinfunction "2_2") (pintype "passive"))
    )
    (net (code "44") (name "unconnected-(MDL1-CS0-Pad17)") (class "Default")
      (node (ref "MDL1") (pin "17") (pinfunction "CS0_17") (pintype "bidirectional"))
    )
    (net (code "45") (name "unconnected-(MDL1-GPIO9-Pad19)") (class "Default")
      (node (ref "MDL1") (pin "19") (pinfunction "GPIO9_19") (pintype "bidirectional"))
    )
    (net (code "46") (name "unconnected-(MDL1-GPIO10-Pad20)") (class "Default")
      (node (ref "MDL1") (pin "20") (pinfunction "GPIO10_20") (pintype "bidirectional"))
    )
    (net (code "47") (name "unconnected-(MDL1-MISO-Pad18)") (class "Default")
      (node (ref "MDL1") (pin "18") (pinfunction "MISO_18") (pintype "bidirectional"))
    )
    (net (code "48") (name "unconnected-(MDL1-MOSI-Pad21)") (class "Default")
      (node (ref "MDL1") (pin "21") (pinfunction "MOSI_21") (pintype "bidirectional"))
    )
    (net (code "49") (name "unconnected-(MDL1-SCLK-Pad22)") (class "Default")
      (node (ref "MDL1") (pin "22") (pinfunction "SCLK_22") (pintype "bidirectional"))
    )
  )
)
